# 4.net
KiCad netlist of a schematic drawn in Altium Designer
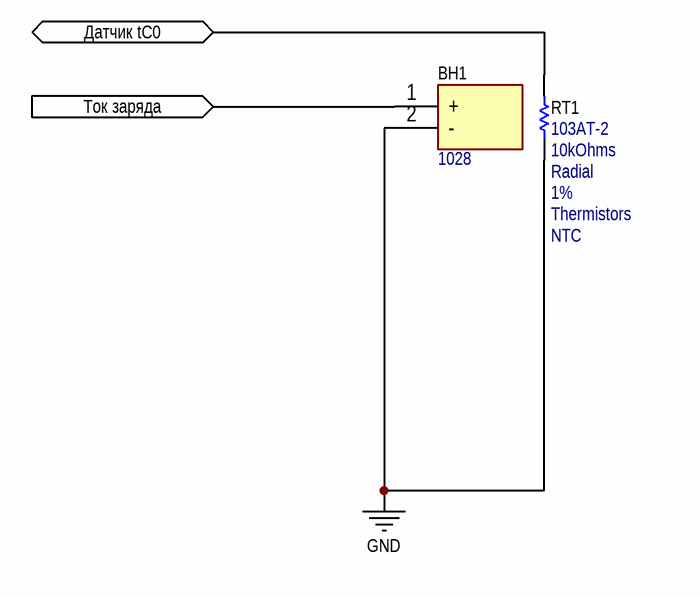
[diagram p0: Блок4.SchDoc]

(export (version "E")
  (design (tool "Eeschema 10.0.6"))
  (components
    (comp (ref "BH1")
      (value "1028")
      (footprint "SamacSys:1028")
      (description "Undefined or Miscellaneous")
      (fields (field (name "MOUSER PART NUMBER") "534-1028"))
      (libsource (lib "*") (part "1028"))
    )
    (comp (ref "RT1")
      (value "103AT-2")
      (footprint "SEMI-103AT-2_V")
      (description "Precision NTC Thermistor, 10 kOhm, +/- 1%, 10 mW, -50 to 110 degC, 2-Pin THD, RoHS, Bulk")
      (fields
        (field (name "MANUFACTURER") "Semitec")
        (field (name "RESISTANCE") "10kOhms")
        (field (name "TERMINATION STYLE") "Radial")
        (field (name "TOLERANCE") "1%")
        (field (name "PRODUCT CATEGORY") "Thermistors")
        (field (name "TYPE") "NTC")
      )
      (libsource (lib "Altium Content Vault") (part "RES-THERMAL-2"))
    )
  )
  (nets
    (net (code "1") (name "/Датчик tC0") (class "Default")
      (node (ref "RT1") (pin "2") (pinfunction "2_2") (pintype "passive"))
    )
    (net (code "2") (name "/Ток заряда") (class "Default")
      (node (ref "BH1") (pin "1") (pinfunction "+_1") (pintype "passive"))
    )
    (net (code "3") (name "GND") (class "Default")
      (node (ref "BH1") (pin "2") (pinfunction "-_2") (pintype "passive"))
      (node (ref "RT1") (pin "1") (pinfunction "1_1") (pintype "passive"))
    )
  )
)
